# Sheet7.net
KiCad netlist of a schematic drawn in Altium Designer
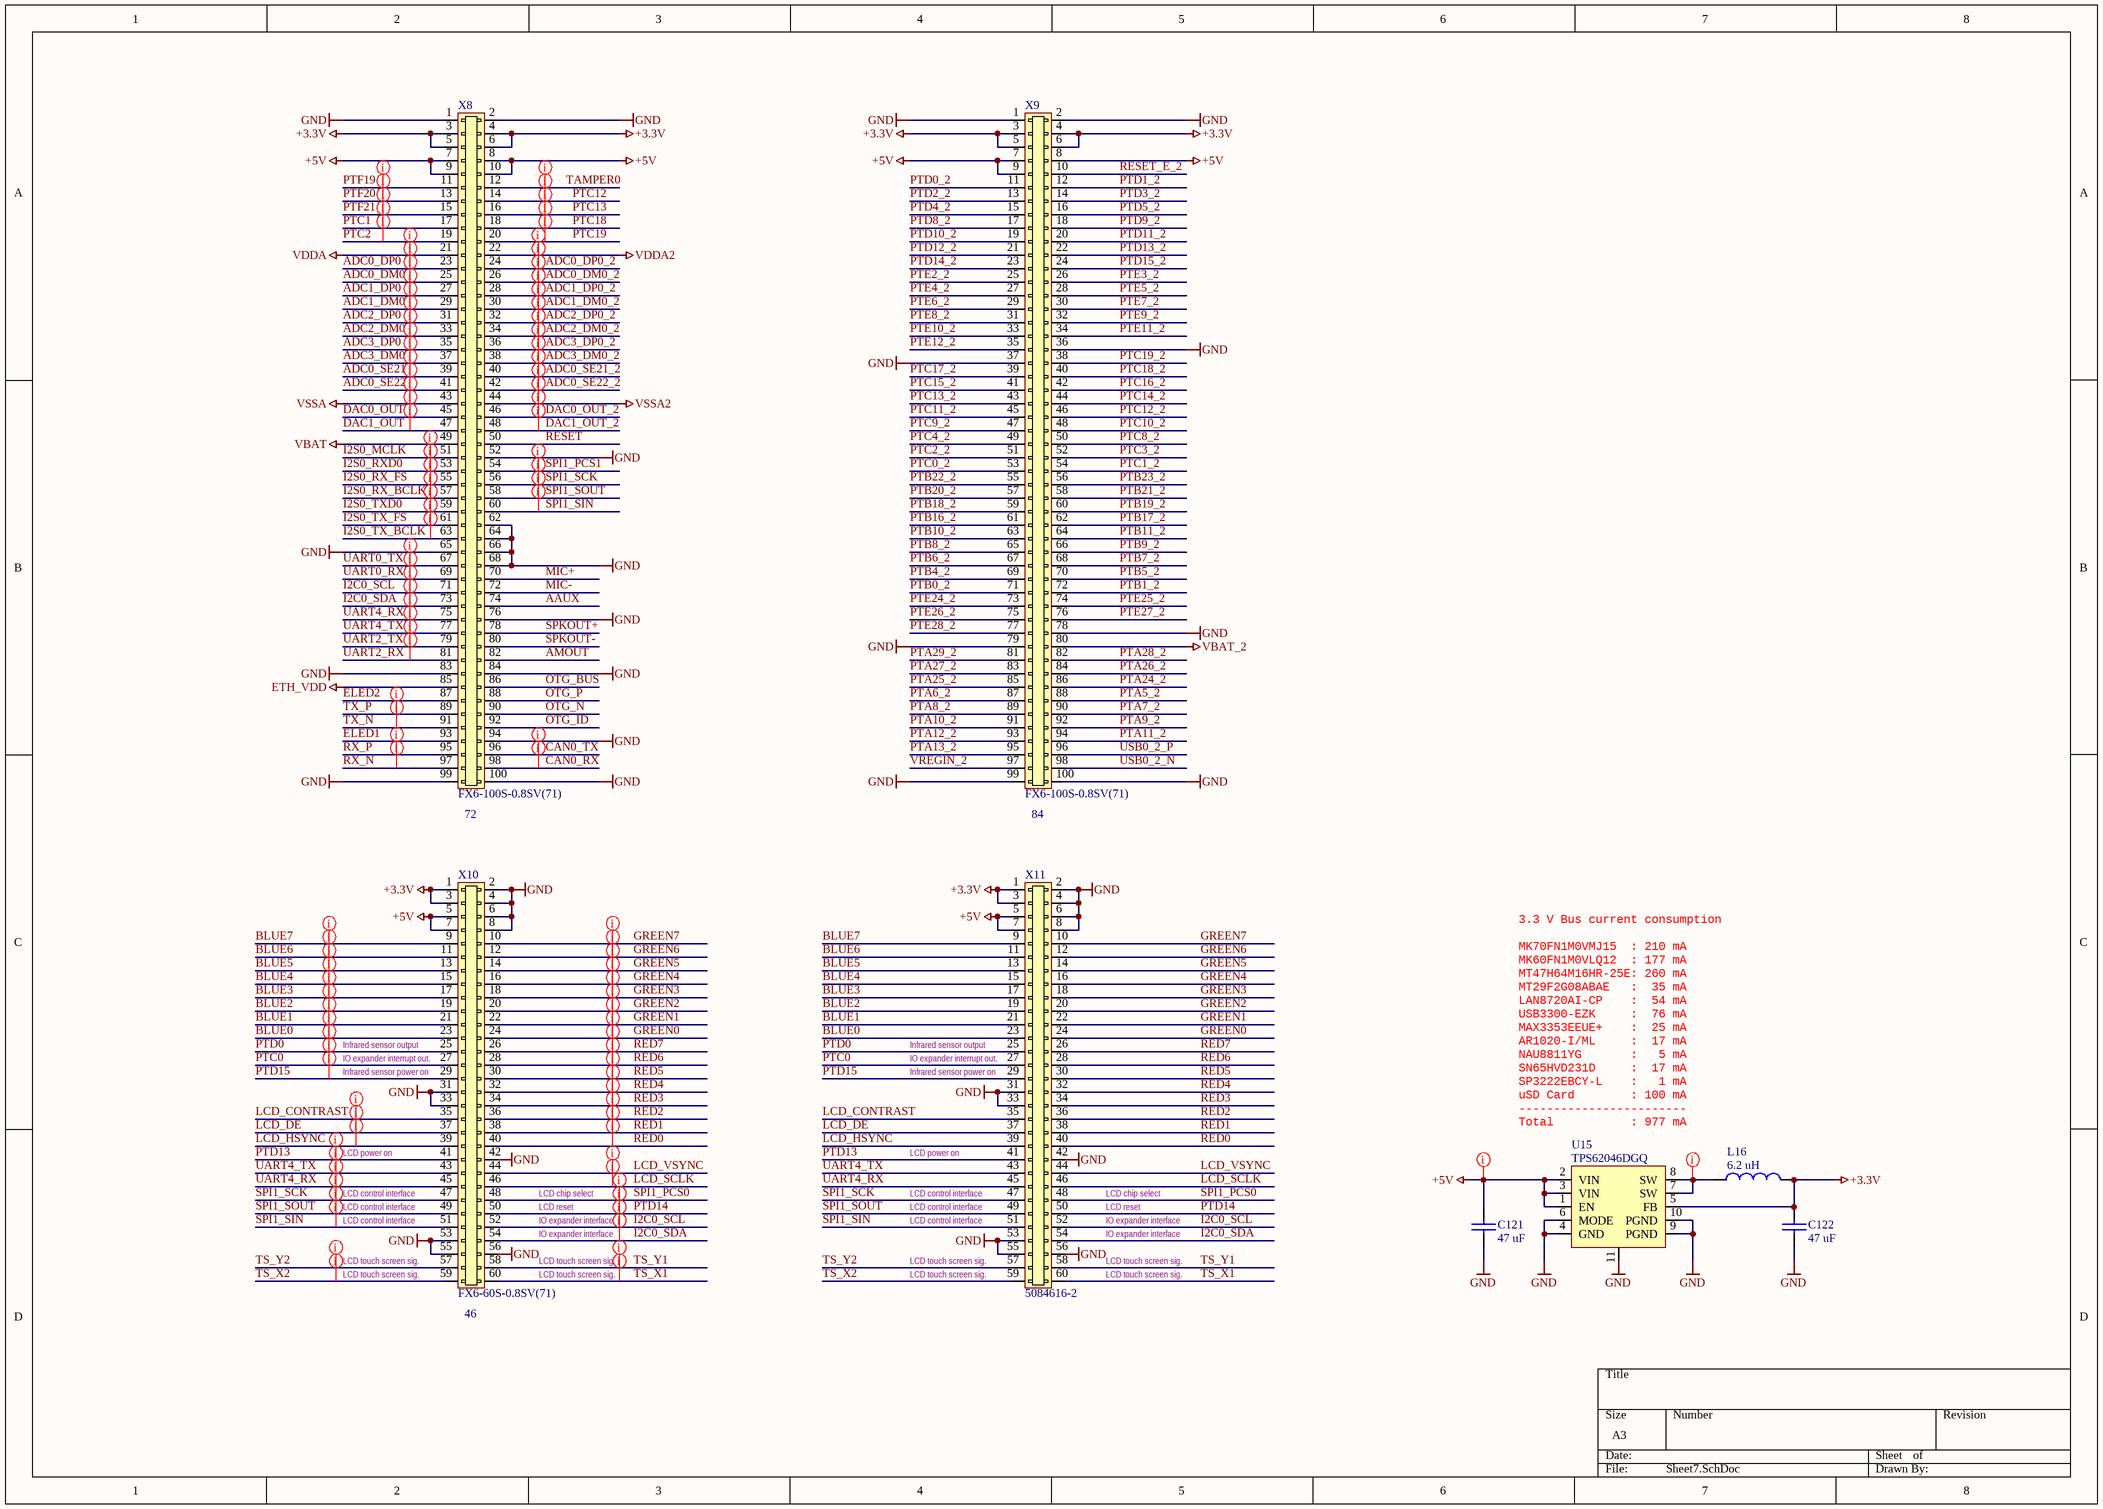
[diagram p0: Sheet7.SchDoc]

(export (version "E")
  (design (tool "Eeschema 10.0.6"))
  (components
    (comp (ref "C121")
      (value "47 uF")
      (footprint "3225[1210]")
      (description "47.0 uF, 10V, 10%, X7R, 1210")
      (fields
        (field (name "MANUFACTURER") "Murata Electronics North America")
        (field (name "TOLERANCE") "10%")
      )
      (libsource (lib "ea_Capacitors") (part "GRM32ER71A476KE15L"))
    )
    (comp (ref "C122")
      (value "47 uF")
      (footprint "3225[1210]")
      (description "47.0 uF, 10V, 10%, X7R, 1210")
      (fields
        (field (name "MANUFACTURER") "Murata Electronics North America")
        (field (name "TOLERANCE") "10%")
      )
      (libsource (lib "ea_Capacitors") (part "GRM32ER71A476KE15L"))
    )
    (comp (ref "L16")
      (value "6.2 uH")
      (footprint "CDRH6D38")
      (description "INDUCTOR POWER 6.2UH 2.50A SMD")
      (fields
        (field (name "MANUFACTURER") "Sumida America Components Inc")
        (field (name "PARTNUM") "308-2315-1-ND")
      )
      (libsource (lib "ea_Inductors") (part "CDRH6D38NP-6R2NC"))
    )
    (comp (ref "U15")
      (value "TPS62046DGQ")
      (footprint "TI-DGQ 10pin (R-PDSO-G10)")
      (description "REG BUCK SYNC 3.3V , 2.5..6V, 1.2A, -40..85 C, 10MSOP")
      (fields (field (name "MANUFACTURER") "Texas Instruments") (field (name "PARTNUM") "296-27023-5-ND"))
      (libsource (lib "ea_IC_Power_Reg_Ref_Sw") (part "TPS62046DGQ"))
    )
    (comp (ref "X8")
      (value "FX6-100S-0.8SV(71)")
      (footprint "FX6-100S-0.8SV(71)")
      (description "RECEPT 100POS .8MM SMD GOLD, 5mm, 6mm, 7 mm")
      (fields (field (name "MANUFACTURER") "Hirose Electric Co Ltd") (field (name "PARTNUM") "H10808-ND"))
      (libsource (lib "ea_Connectors") (part "FX6-100S-0.8SV(71)"))
    )
    (comp (ref "X9")
      (value "FX6-100S-0.8SV(71)")
      (footprint "FX6-100S-0.8SV(71)")
      (description "RECEPT 100POS .8MM SMD GOLD, 5mm, 6mm, 7 mm")
      (fields (field (name "MANUFACTURER") "Hirose Electric Co Ltd") (field (name "PARTNUM") "H10808-ND"))
      (libsource (lib "ea_Connectors") (part "FX6-100S-0.8SV(71)"))
    )
    (comp (ref "X10")
      (value "FX6-60S-0.8SV(71)")
      (footprint "FX6-60S-0.8SV(71)")
      (description "RECEPT 60POS .8MM W/BOSS")
      (fields (field (name "MANUFACTURER") "Hirose Electric Co Ltd") (field (name "PARTNUM") "H10806-ND"))
      (libsource (lib "ea_Connectors") (part "FX6-60S-0.8SV(71)"))
    )
    (comp (ref "X11")
      (value "5084616-2")
      (footprint "5084616-2")
      (description "Free Height (FH) Connectors 60P 13mm RECEPTACLE STACK HEIGHT 13-16mm")
      (fields (field (name "MANUFACTURER") "Tyco Electronics / AMP") (field (name "PARTNUM") "A99235CT-ND"))
      (libsource (lib "ea_Connectors") (part "5084616-2"))
    )
  )
  (nets
    (net (code "1") (name "+3.3V") (class "Default")
      (node (ref "C122") (pin "1") (pinfunction "1_1") (pintype "passive"))
      (node (ref "L16") (pin "2") (pinfunction "2_2") (pintype "passive"))
      (node (ref "U15") (pin "5") (pinfunction "FB_5") (pintype "passive"))
      (node (ref "X10") (pin "1") (pinfunction "1_1") (pintype "passive"))
      (node (ref "X10") (pin "3") (pinfunction "2_3") (pintype "passive"))
      (node (ref "X11") (pin "1") (pinfunction "1_1") (pintype "passive"))
      (node (ref "X11") (pin "3") (pinfunction "2_3") (pintype "passive"))
      (node (ref "X8") (pin "3") (pinfunction "2_3") (pintype "passive"))
      (node (ref "X8") (pin "4") (pinfunction "3_4") (pintype "passive"))
      (node (ref "X8") (pin "5") (pinfunction "3_5") (pintype "passive"))
      (node (ref "X8") (pin "6") (pinfunction "4_6") (pintype "passive"))
      (node (ref "X9") (pin "3") (pinfunction "2_3") (pintype "passive"))
      (node (ref "X9") (pin "4") (pinfunction "3_4") (pintype "passive"))
      (node (ref "X9") (pin "5") (pinfunction "3_5") (pintype "passive"))
      (node (ref "X9") (pin "6") (pinfunction "4_6") (pintype "passive"))
    )
    (net (code "2") (name "+5V") (class "Default")
      (node (ref "C121") (pin "1") (pinfunction "1_1") (pintype "passive"))
      (node (ref "U15") (pin "1") (pinfunction "EN_1") (pintype "passive"))
      (node (ref "U15") (pin "2") (pinfunction "VIN_2") (pintype "passive"))
      (node (ref "U15") (pin "3") (pinfunction "VIN_3") (pintype "passive"))
      (node (ref "X10") (pin "5") (pinfunction "3_5") (pintype "passive"))
      (node (ref "X10") (pin "7") (pinfunction "4_7") (pintype "passive"))
      (node (ref "X11") (pin "5") (pinfunction "3_5") (pintype "passive"))
      (node (ref "X11") (pin "7") (pinfunction "4_7") (pintype "passive"))
      (node (ref "X8") (pin "10") (pinfunction "6_10") (pintype "passive"))
      (node (ref "X8") (pin "7") (pinfunction "4_7") (pintype "passive"))
      (node (ref "X8") (pin "8") (pinfunction "5_8") (pintype "passive"))
      (node (ref "X8") (pin "9") (pinfunction "5_9") (pintype "passive"))
      (node (ref "X9") (pin "7") (pinfunction "4_7") (pintype "passive"))
      (node (ref "X9") (pin "8") (pinfunction "5_8") (pintype "passive"))
      (node (ref "X9") (pin "9") (pinfunction "5_9") (pintype "passive"))
    )
    (net (code "3") (name "/AAUX") (class "Default")
      (node (ref "X8") (pin "74") (pinfunction "38_74") (pintype "passive"))
    )
    (net (code "4") (name "/ADC0_DM0") (class "Default")
      (node (ref "X8") (pin "25") (pinfunction "13_25") (pintype "passive"))
    )
    (net (code "5") (name "/ADC0_DM0_2") (class "Default")
      (node (ref "X8") (pin "26") (pinfunction "14_26") (pintype "passive"))
    )
    (net (code "6") (name "/ADC0_DP0") (class "Default")
      (node (ref "X8") (pin "23") (pinfunction "12_23") (pintype "passive"))
    )
    (net (code "7") (name "/ADC0_DP0_2") (class "Default")
      (node (ref "X8") (pin "24") (pinfunction "13_24") (pintype "passive"))
    )
    (net (code "8") (name "/ADC0_SE21") (class "Default")
      (node (ref "X8") (pin "39") (pinfunction "20_39") (pintype "passive"))
    )
    (net (code "9") (name "/ADC0_SE21_2") (class "Default")
      (node (ref "X8") (pin "40") (pinfunction "21_40") (pintype "passive"))
    )
    (net (code "10") (name "/ADC0_SE22") (class "Default")
      (node (ref "X8") (pin "41") (pinfunction "21_41") (pintype "passive"))
    )
    (net (code "11") (name "/ADC0_SE22_2") (class "Default")
      (node (ref "X8") (pin "42") (pinfunction "22_42") (pintype "passive"))
    )
    (net (code "12") (name "/ADC1_DM0") (class "Default")
      (node (ref "X8") (pin "29") (pinfunction "15_29") (pintype "passive"))
    )
    (net (code "13") (name "/ADC1_DM0_2") (class "Default")
      (node (ref "X8") (pin "30") (pinfunction "16_30") (pintype "passive"))
    )
    (net (code "14") (name "/ADC1_DP0") (class "Default")
      (node (ref "X8") (pin "27") (pinfunction "14_27") (pintype "passive"))
    )
    (net (code "15") (name "/ADC1_DP0_2") (class "Default")
      (node (ref "X8") (pin "28") (pinfunction "15_28") (pintype "passive"))
    )
    (net (code "16") (name "/ADC2_DM0") (class "Default")
      (node (ref "X8") (pin "33") (pinfunction "17_33") (pintype "passive"))
    )
    (net (code "17") (name "/ADC2_DM0_2") (class "Default")
      (node (ref "X8") (pin "34") (pinfunction "18_34") (pintype "passive"))
    )
    (net (code "18") (name "/ADC2_DP0") (class "Default")
      (node (ref "X8") (pin "31") (pinfunction "16_31") (pintype "passive"))
    )
    (net (code "19") (name "/ADC2_DP0_2") (class "Default")
      (node (ref "X8") (pin "32") (pinfunction "17_32") (pintype "passive"))
    )
    (net (code "20") (name "/ADC3_DM0") (class "Default")
      (node (ref "X8") (pin "37") (pinfunction "19_37") (pintype "passive"))
    )
    (net (code "21") (name "/ADC3_DM0_2") (class "Default")
      (node (ref "X8") (pin "38") (pinfunction "20_38") (pintype "passive"))
    )
    (net (code "22") (name "/ADC3_DP0") (class "Default")
      (node (ref "X8") (pin "35") (pinfunction "18_35") (pintype "passive"))
    )
    (net (code "23") (name "/ADC3_DP0_2") (class "Default")
      (node (ref "X8") (pin "36") (pinfunction "19_36") (pintype "passive"))
    )
    (net (code "24") (name "/AMOUT") (class "Default")
      (node (ref "X8") (pin "82") (pinfunction "42_82") (pintype "passive"))
    )
    (net (code "25") (name "/BLUE0") (class "Default")
      (node (ref "X10") (pin "23") (pinfunction "12_23") (pintype "passive"))
      (node (ref "X11") (pin "23") (pinfunction "12_23") (pintype "passive"))
    )
    (net (code "26") (name "/BLUE1") (class "Default")
      (node (ref "X10") (pin "21") (pinfunction "11_21") (pintype "passive"))
      (node (ref "X11") (pin "21") (pinfunction "11_21") (pintype "passive"))
    )
    (net (code "27") (name "/BLUE2") (class "Default")
      (node (ref "X10") (pin "19") (pinfunction "10_19") (pintype "passive"))
      (node (ref "X11") (pin "19") (pinfunction "10_19") (pintype "passive"))
    )
    (net (code "28") (name "/BLUE3") (class "Default")
      (node (ref "X10") (pin "17") (pinfunction "9_17") (pintype "passive"))
      (node (ref "X11") (pin "17") (pinfunction "9_17") (pintype "passive"))
    )
    (net (code "29") (name "/BLUE4") (class "Default")
      (node (ref "X10") (pin "15") (pinfunction "8_15") (pintype "passive"))
      (node (ref "X11") (pin "15") (pinfunction "8_15") (pintype "passive"))
    )
    (net (code "30") (name "/BLUE5") (class "Default")
      (node (ref "X10") (pin "13") (pinfunction "7_13") (pintype "passive"))
      (node (ref "X11") (pin "13") (pinfunction "7_13") (pintype "passive"))
    )
    (net (code "31") (name "/BLUE6") (class "Default")
      (node (ref "X10") (pin "11") (pinfunction "6_11") (pintype "passive"))
      (node (ref "X11") (pin "11") (pinfunction "6_11") (pintype "passive"))
    )
    (net (code "32") (name "/BLUE7") (class "Default")
      (node (ref "X10") (pin "9") (pinfunction "5_9") (pintype "passive"))
      (node (ref "X11") (pin "9") (pinfunction "5_9") (pintype "passive"))
    )
    (net (code "33") (name "/CAN0_RX") (class "Default")
      (node (ref "X8") (pin "98") (pinfunction "50_98") (pintype "passive"))
    )
    (net (code "34") (name "/CAN0_TX") (class "Default")
      (node (ref "X8") (pin "96") (pinfunction "49_96") (pintype "passive"))
    )
    (net (code "35") (name "/DAC0_OUT") (class "Default")
      (node (ref "X8") (pin "45") (pinfunction "23_45") (pintype "passive"))
    )
    (net (code "36") (name "/DAC0_OUT_2") (class "Default")
      (node (ref "X8") (pin "46") (pinfunction "24_46") (pintype "passive"))
    )
    (net (code "37") (name "/DAC1_OUT") (class "Default")
      (node (ref "X8") (pin "47") (pinfunction "24_47") (pintype "passive"))
    )
    (net (code "38") (name "/DAC1_OUT_2") (class "Default")
      (node (ref "X8") (pin "48") (pinfunction "25_48") (pintype "passive"))
    )
    (net (code "39") (name "/ELED1") (class "Default")
      (node (ref "X8") (pin "93") (pinfunction "47_93") (pintype "passive"))
    )
    (net (code "40") (name "/ELED2") (class "Default")
      (node (ref "X8") (pin "87") (pinfunction "44_87") (pintype "passive"))
    )
    (net (code "41") (name "/GREEN0") (class "Default")
      (node (ref "X10") (pin "24") (pinfunction "13_24") (pintype "passive"))
      (node (ref "X11") (pin "24") (pinfunction "13_24") (pintype "passive"))
    )
    (net (code "42") (name "/GREEN1") (class "Default")
      (node (ref "X10") (pin "22") (pinfunction "12_22") (pintype "passive"))
      (node (ref "X11") (pin "22") (pinfunction "12_22") (pintype "passive"))
    )
    (net (code "43") (name "/GREEN2") (class "Default")
      (node (ref "X10") (pin "20") (pinfunction "11_20") (pintype "passive"))
      (node (ref "X11") (pin "20") (pinfunction "11_20") (pintype "passive"))
    )
    (net (code "44") (name "/GREEN3") (class "Default")
      (node (ref "X10") (pin "18") (pinfunction "10_18") (pintype "passive"))
      (node (ref "X11") (pin "18") (pinfunction "10_18") (pintype "passive"))
    )
    (net (code "45") (name "/GREEN4") (class "Default")
      (node (ref "X10") (pin "16") (pinfunction "9_16") (pintype "passive"))
      (node (ref "X11") (pin "16") (pinfunction "9_16") (pintype "passive"))
    )
    (net (code "46") (name "/GREEN5") (class "Default")
      (node (ref "X10") (pin "14") (pinfunction "8_14") (pintype "passive"))
      (node (ref "X11") (pin "14") (pinfunction "8_14") (pintype "passive"))
    )
    (net (code "47") (name "/GREEN6") (class "Default")
      (node (ref "X10") (pin "12") (pinfunction "7_12") (pintype "passive"))
      (node (ref "X11") (pin "12") (pinfunction "7_12") (pintype "passive"))
    )
    (net (code "48") (name "/GREEN7") (class "Default")
      (node (ref "X10") (pin "10") (pinfunction "6_10") (pintype "passive"))
      (node (ref "X11") (pin "10") (pinfunction "6_10") (pintype "passive"))
    )
    (net (code "49") (name "/I2C0_SCL") (class "Default")
      (node (ref "X10") (pin "52") (pinfunction "27_52") (pintype "passive"))
      (node (ref "X11") (pin "52") (pinfunction "27_52") (pintype "passive"))
      (node (ref "X8") (pin "71") (pinfunction "36_71") (pintype "passive"))
    )
    (net (code "50") (name "/I2C0_SDA") (class "Default")
      (node (ref "X10") (pin "54") (pinfunction "28_54") (pintype "passive"))
      (node (ref "X11") (pin "54") (pinfunction "28_54") (pintype "passive"))
      (node (ref "X8") (pin "73") (pinfunction "37_73") (pintype "passive"))
    )
    (net (code "51") (name "/I2S0_MCLK") (class "Default")
      (node (ref "X8") (pin "51") (pinfunction "26_51") (pintype "passive"))
    )
    (net (code "52") (name "/I2S0_RXD0") (class "Default")
      (node (ref "X8") (pin "53") (pinfunction "27_53") (pintype "passive"))
    )
    (net (code "53") (name "/I2S0_RX_BCLK") (class "Default")
      (node (ref "X8") (pin "57") (pinfunction "29_57") (pintype "passive"))
    )
    (net (code "54") (name "/I2S0_RX_FS") (class "Default")
      (node (ref "X8") (pin "55") (pinfunction "28_55") (pintype "passive"))
    )
    (net (code "55") (name "/I2S0_TXD0") (class "Default")
      (node (ref "X8") (pin "59") (pinfunction "30_59") (pintype "passive"))
    )
    (net (code "56") (name "/I2S0_TX_BCLK") (class "Default")
      (node (ref "X8") (pin "63") (pinfunction "32_63") (pintype "passive"))
    )
    (net (code "57") (name "/I2S0_TX_FS") (class "Default")
      (node (ref "X8") (pin "61") (pinfunction "31_61") (pintype "passive"))
    )
    (net (code "58") (name "/LCD_CONTRAST") (class "Default")
      (node (ref "X10") (pin "35") (pinfunction "18_35") (pintype "passive"))
      (node (ref "X11") (pin "35") (pinfunction "18_35") (pintype "passive"))
    )
    (net (code "59") (name "/LCD_DE") (class "Default")
      (node (ref "X10") (pin "37") (pinfunction "19_37") (pintype "passive"))
      (node (ref "X11") (pin "37") (pinfunction "19_37") (pintype "passive"))
    )
    (net (code "60") (name "/LCD_HSYNC") (class "Default")
      (node (ref "X10") (pin "39") (pinfunction "20_39") (pintype "passive"))
      (node (ref "X11") (pin "39") (pinfunction "20_39") (pintype "passive"))
    )
    (net (code "61") (name "/LCD_SCLK") (class "Default")
      (node (ref "X10") (pin "46") (pinfunction "24_46") (pintype "passive"))
      (node (ref "X11") (pin "46") (pinfunction "24_46") (pintype "passive"))
    )
    (net (code "62") (name "/LCD_VSYNC") (class "Default")
      (node (ref "X10") (pin "44") (pinfunction "23_44") (pintype "passive"))
      (node (ref "X11") (pin "44") (pinfunction "23_44") (pintype "passive"))
    )
    (net (code "63") (name "/MIC+") (class "Default")
      (node (ref "X8") (pin "70") (pinfunction "36_70") (pintype "passive"))
    )
    (net (code "64") (name "/MIC-") (class "Default")
      (node (ref "X8") (pin "72") (pinfunction "37_72") (pintype "passive"))
    )
    (net (code "65") (name "/OTG_BUS") (class "Default")
      (node (ref "X8") (pin "86") (pinfunction "44_86") (pintype "passive"))
    )
    (net (code "66") (name "/OTG_ID") (class "Default")
      (node (ref "X8") (pin "92") (pinfunction "47_92") (pintype "passive"))
    )
    (net (code "67") (name "/OTG_N") (class "Default")
      (node (ref "X8") (pin "90") (pinfunction "46_90") (pintype "passive"))
    )
    (net (code "68") (name "/OTG_P") (class "Default")
      (node (ref "X8") (pin "88") (pinfunction "45_88") (pintype "passive"))
    )
    (net (code "69") (name "/PTA5_2") (class "Default")
      (node (ref "X9") (pin "88") (pinfunction "45_88") (pintype "passive"))
    )
    (net (code "70") (name "/PTA6_2") (class "Default")
      (node (ref "X9") (pin "87") (pinfunction "44_87") (pintype "passive"))
    )
    (net (code "71") (name "/PTA7_2") (class "Default")
      (node (ref "X9") (pin "90") (pinfunction "46_90") (pintype "passive"))
    )
    (net (code "72") (name "/PTA8_2") (class "Default")
      (node (ref "X9") (pin "89") (pinfunction "45_89") (pintype "passive"))
    )
    (net (code "73") (name "/PTA9_2") (class "Default")
      (node (ref "X9") (pin "92") (pinfunction "47_92") (pintype "passive"))
    )
    (net (code "74") (name "/PTA10_2") (class "Default")
      (node (ref "X9") (pin "91") (pinfunction "46_91") (pintype "passive"))
    )
    (net (code "75") (name "/PTA11_2") (class "Default")
      (node (ref "X9") (pin "94") (pinfunction "48_94") (pintype "passive"))
    )
    (net (code "76") (name "/PTA12_2") (class "Default")
      (node (ref "X9") (pin "93") (pinfunction "47_93") (pintype "passive"))
    )
    (net (code "77") (name "/PTA13_2") (class "Default")
      (node (ref "X9") (pin "95") (pinfunction "48_95") (pintype "passive"))
    )
    (net (code "78") (name "/PTA24_2") (class "Default")
      (node (ref "X9") (pin "86") (pinfunction "44_86") (pintype "passive"))
    )
    (net (code "79") (name "/PTA25_2") (class "Default")
      (node (ref "X9") (pin "85") (pinfunction "43_85") (pintype "passive"))
    )
    (net (code "80") (name "/PTA26_2") (class "Default")
      (node (ref "X9") (pin "84") (pinfunction "43_84") (pintype "passive"))
    )
    (net (code "81") (name "/PTA27_2") (class "Default")
      (node (ref "X9") (pin "83") (pinfunction "42_83") (pintype "passive"))
    )
    (net (code "82") (name "/PTA28_2") (class "Default")
      (node (ref "X9") (pin "82") (pinfunction "42_82") (pintype "passive"))
    )
    (net (code "83") (name "/PTA29_2") (class "Default")
      (node (ref "X9") (pin "81") (pinfunction "41_81") (pintype "passive"))
    )
    (net (code "84") (name "/PTB0_2") (class "Default")
      (node (ref "X9") (pin "71") (pinfunction "36_71") (pintype "passive"))
    )
    (net (code "85") (name "/PTB1_2") (class "Default")
      (node (ref "X9") (pin "72") (pinfunction "37_72") (pintype "passive"))
    )
    (net (code "86") (name "/PTB4_2") (class "Default")
      (node (ref "X9") (pin "69") (pinfunction "35_69") (pintype "passive"))
    )
    (net (code "87") (name "/PTB5_2") (class "Default")
      (node (ref "X9") (pin "70") (pinfunction "36_70") (pintype "passive"))
    )
    (net (code "88") (name "/PTB6_2") (class "Default")
      (node (ref "X9") (pin "67") (pinfunction "34_67") (pintype "passive"))
    )
    (net (code "89") (name "/PTB7_2") (class "Default")
      (node (ref "X9") (pin "68") (pinfunction "35_68") (pintype "passive"))
    )
    (net (code "90") (name "/PTB8_2") (class "Default")
      (node (ref "X9") (pin "65") (pinfunction "33_65") (pintype "passive"))
    )
    (net (code "91") (name "/PTB9_2") (class "Default")
      (node (ref "X9") (pin "66") (pinfunction "34_66") (pintype "passive"))
    )
    (net (code "92") (name "/PTB10_2") (class "Default")
      (node (ref "X9") (pin "63") (pinfunction "32_63") (pintype "passive"))
    )
    (net (code "93") (name "/PTB11_2") (class "Default")
      (node (ref "X9") (pin "64") (pinfunction "33_64") (pintype "passive"))
    )
    (net (code "94") (name "/PTB16_2") (class "Default")
      (node (ref "X9") (pin "61") (pinfunction "31_61") (pintype "passive"))
    )
    (net (code "95") (name "/PTB17_2") (class "Default")
      (node (ref "X9") (pin "62") (pinfunction "32_62") (pintype "passive"))
    )
    (net (code "96") (name "/PTB18_2") (class "Default")
      (node (ref "X9") (pin "59") (pinfunction "30_59") (pintype "passive"))
    )
    (net (code "97") (name "/PTB19_2") (class "Default")
      (node (ref "X9") (pin "60") (pinfunction "31_60") (pintype "passive"))
    )
    (net (code "98") (name "/PTB20_2") (class "Default")
      (node (ref "X9") (pin "57") (pinfunction "29_57") (pintype "passive"))
    )
    (net (code "99") (name "/PTB21_2") (class "Default")
      (node (ref "X9") (pin "58") (pinfunction "30_58") (pintype "passive"))
    )
    (net (code "100") (name "/PTB22_2") (class "Default")
      (node (ref "X9") (pin "55") (pinfunction "28_55") (pintype "passive"))
    )
    (net (code "101") (name "/PTB23_2") (class "Default")
      (node (ref "X9") (pin "56") (pinfunction "29_56") (pintype "passive"))
    )
    (net (code "102") (name "/PTC0") (class "Default")
      (node (ref "X10") (pin "27") (pinfunction "14_27") (pintype "passive"))
      (node (ref "X11") (pin "27") (pinfunction "14_27") (pintype "passive"))
    )
    (net (code "103") (name "/PTC0_2") (class "Default")
      (node (ref "X9") (pin "53") (pinfunction "27_53") (pintype "passive"))
    )
    (net (code "104") (name "/PTC1") (class "Default")
      (node (ref "X8") (pin "17") (pinfunction "9_17") (pintype "passive"))
    )
    (net (code "105") (name "/PTC1_2") (class "Default")
      (node (ref "X9") (pin "54") (pinfunction "28_54") (pintype "passive"))
    )
    (net (code "106") (name "/PTC2") (class "Default")
      (node (ref "X8") (pin "19") (pinfunction "10_19") (pintype "passive"))
    )
    (net (code "107") (name "/PTC2_2") (class "Default")
      (node (ref "X9") (pin "51") (pinfunction "26_51") (pintype "passive"))
    )
    (net (code "108") (name "/PTC3_2") (class "Default")
      (node (ref "X9") (pin "52") (pinfunction "27_52") (pintype "passive"))
    )
    (net (code "109") (name "/PTC4_2") (class "Default")
      (node (ref "X9") (pin "49") (pinfunction "25_49") (pintype "passive"))
    )
    (net (code "110") (name "/PTC8_2") (class "Default")
      (node (ref "X9") (pin "50") (pinfunction "26_50") (pintype "passive"))
    )
    (net (code "111") (name "/PTC9_2") (class "Default")
      (node (ref "X9") (pin "47") (pinfunction "24_47") (pintype "passive"))
    )
    (net (code "112") (name "/PTC10_2") (class "Default")
      (node (ref "X9") (pin "48") (pinfunction "25_48") (pintype "passive"))
    )
    (net (code "113") (name "/PTC11_2") (class "Default")
      (node (ref "X9") (pin "45") (pinfunction "23_45") (pintype "passive"))
    )
    (net (code "114") (name "/PTC12") (class "Default")
      (node (ref "X8") (pin "14") (pinfunction "8_14") (pintype "passive"))
    )
    (net (code "115") (name "/PTC12_2") (class "Default")
      (node (ref "X9") (pin "46") (pinfunction "24_46") (pintype "passive"))
    )
    (net (code "116") (name "/PTC13") (class "Default")
      (node (ref "X8") (pin "16") (pinfunction "9_16") (pintype "passive"))
    )
    (net (code "117") (name "/PTC13_2") (class "Default")
      (node (ref "X9") (pin "43") (pinfunction "22_43") (pintype "passive"))
    )
    (net (code "118") (name "/PTC14_2") (class "Default")
      (node (ref "X9") (pin "44") (pinfunction "23_44") (pintype "passive"))
    )
    (net (code "119") (name "/PTC15_2") (class "Default")
      (node (ref "X9") (pin "41") (pinfunction "21_41") (pintype "passive"))
    )
    (net (code "120") (name "/PTC16_2") (class "Default")
      (node (ref "X9") (pin "42") (pinfunction "22_42") (pintype "passive"))
    )
    (net (code "121") (name "/PTC17_2") (class "Default")
      (node (ref "X9") (pin "39") (pinfunction "20_39") (pintype "passive"))
    )
    (net (code "122") (name "/PTC18") (class "Default")
      (node (ref "X8") (pin "18") (pinfunction "10_18") (pintype "passive"))
    )
    (net (code "123") (name "/PTC18_2") (class "Default")
      (node (ref "X9") (pin "40") (pinfunction "21_40") (pintype "passive"))
    )
    (net (code "124") (name "/PTC19") (class "Default")
      (node (ref "X8") (pin "20") (pinfunction "11_20") (pintype "passive"))
    )
    (net (code "125") (name "/PTC19_2") (class "Default")
      (node (ref "X9") (pin "38") (pinfunction "20_38") (pintype "passive"))
    )
    (net (code "126") (name "/PTD0") (class "Default")
      (node (ref "X10") (pin "25") (pinfunction "13_25") (pintype "passive"))
      (node (ref "X11") (pin "25") (pinfunction "13_25") (pintype "passive"))
    )
    (net (code "127") (name "/PTD0_2") (class "Default")
      (node (ref "X9") (pin "11") (pinfunction "6_11") (pintype "passive"))
    )
    (net (code "128") (name "/PTD1_2") (class "Default")
      (node (ref "X9") (pin "12") (pinfunction "7_12") (pintype "passive"))
    )
    (net (code "129") (name "/PTD2_2") (class "Default")
      (node (ref "X9") (pin "13") (pinfunction "7_13") (pintype "passive"))
    )
    (net (code "130") (name "/PTD3_2") (class "Default")
      (node (ref "X9") (pin "14") (pinfunction "8_14") (pintype "passive"))
    )
    (net (code "131") (name "/PTD4_2") (class "Default")
      (node (ref "X9") (pin "15") (pinfunction "8_15") (pintype "passive"))
    )
    (net (code "132") (name "/PTD5_2") (class "Default")
      (node (ref "X9") (pin "16") (pinfunction "9_16") (pintype "passive"))
    )
    (net (code "133") (name "/PTD8_2") (class "Default")
      (node (ref "X9") (pin "17") (pinfunction "9_17") (pintype "passive"))
    )
    (net (code "134") (name "/PTD9_2") (class "Default")
      (node (ref "X9") (pin "18") (pinfunction "10_18") (pintype "passive"))
    )
    (net (code "135") (name "/PTD10_2") (class "Default")
      (node (ref "X9") (pin "19") (pinfunction "10_19") (pintype "passive"))
    )
    (net (code "136") (name "/PTD11_2") (class "Default")
      (node (ref "X9") (pin "20") (pinfunction "11_20") (pintype "passive"))
    )
    (net (code "137") (name "/PTD12_2") (class "Default")
      (node (ref "X9") (pin "21") (pinfunction "11_21") (pintype "passive"))
    )
    (net (code "138") (name "/PTD13") (class "Default")
      (node (ref "X10") (pin "41") (pinfunction "21_41") (pintype "passive"))
      (node (ref "X11") (pin "41") (pinfunction "21_41") (pintype "passive"))
    )
    (net (code "139") (name "/PTD13_2") (class "Default")
      (node (ref "X9") (pin "22") (pinfunction "12_22") (pintype "passive"))
    )
    (net (code "140") (name "/PTD14") (class "Default")
      (node (ref "X10") (pin "50") (pinfunction "26_50") (pintype "passive"))
      (node (ref "X11") (pin "50") (pinfunction "26_50") (pintype "passive"))
    )
    (net (code "141") (name "/PTD14_2") (class "Default")
      (node (ref "X9") (pin "23") (pinfunction "12_23") (pintype "passive"))
    )
    (net (code "142") (name "/PTD15") (class "Default")
      (node (ref "X10") (pin "29") (pinfunction "15_29") (pintype "passive"))
      (node (ref "X11") (pin "29") (pinfunction "15_29") (pintype "passive"))
    )
    (net (code "143") (name "/PTD15_2") (class "Default")
      (node (ref "X9") (pin "24") (pinfunction "13_24") (pintype "passive"))
    )
    (net (code "144") (name "/PTE2_2") (class "Default")
      (node (ref "X9") (pin "25") (pinfunction "13_25") (pintype "passive"))
    )
    (net (code "145") (name "/PTE3_2") (class "Default")
      (node (ref "X9") (pin "26") (pinfunction "14_26") (pintype "passive"))
    )
    (net (code "146") (name "/PTE4_2") (class "Default")
      (node (ref "X9") (pin "27") (pinfunction "14_27") (pintype "passive"))
    )
    (net (code "147") (name "/PTE5_2") (class "Default")
      (node (ref "X9") (pin "28") (pinfunction "15_28") (pintype "passive"))
    )
    (net (code "148") (name "/PTE6_2") (class "Default")
      (node (ref "X9") (pin "29") (pinfunction "15_29") (pintype "passive"))
    )
    (net (code "149") (name "/PTE7_2") (class "Default")
      (node (ref "X9") (pin "30") (pinfunction "16_30") (pintype "passive"))
    )
    (net (code "150") (name "/PTE8_2") (class "Default")
      (node (ref "X9") (pin "31") (pinfunction "16_31") (pintype "passive"))
    )
    (net (code "151") (name "/PTE9_2") (class "Default")
      (node (ref "X9") (pin "32") (pinfunction "17_32") (pintype "passive"))
    )
    (net (code "152") (name "/PTE10_2") (class "Default")
      (node (ref "X9") (pin "33") (pinfunction "17_33") (pintype "passive"))
    )
    (net (code "153") (name "/PTE11_2") (class "Default")
      (node (ref "X9") (pin "34") (pinfunction "18_34") (pintype "passive"))
    )
    (net (code "154") (name "/PTE12_2") (class "Default")
      (node (ref "X9") (pin "35") (pinfunction "18_35") (pintype "passive"))
    )
    (net (code "155") (name "/PTE24_2") (class "Default")
      (node (ref "X9") (pin "73") (pinfunction "37_73") (pintype "passive"))
    )
    (net (code "156") (name "/PTE25_2") (class "Default")
      (node (ref "X9") (pin "74") (pinfunction "38_74") (pintype "passive"))
    )
    (net (code "157") (name "/PTE26_2") (class "Default")
      (node (ref "X9") (pin "75") (pinfunction "38_75") (pintype "passive"))
    )
    (net (code "158") (name "/PTE27_2") (class "Default")
      (node (ref "X9") (pin "76") (pinfunction "39_76") (pintype "passive"))
    )
    (net (code "159") (name "/PTE28_2") (class "Default")
      (node (ref "X9") (pin "77") (pinfunction "39_77") (pintype "passive"))
    )
    (net (code "160") (name "/PTF19") (class "Default")
      (node (ref "X8") (pin "11") (pinfunction "6_11") (pintype "passive"))
    )
    (net (code "161") (name "/PTF20") (class "Default")
      (node (ref "X8") (pin "13") (pinfunction "7_13") (pintype "passive"))
    )
    (net (code "162") (name "/PTF21") (class "Default")
      (node (ref "X8") (pin "15") (pinfunction "8_15") (pintype "passive"))
    )
    (net (code "163") (name "/RED0") (class "Default")
      (node (ref "X10") (pin "40") (pinfunction "21_40") (pintype "passive"))
      (node (ref "X11") (pin "40") (pinfunction "21_40") (pintype "passive"))
    )
    (net (code "164") (name "/RED1") (class "Default")
      (node (ref "X10") (pin "38") (pinfunction "20_38") (pintype "passive"))
      (node (ref "X11") (pin "38") (pinfunction "20_38") (pintype "passive"))
    )
    (net (code "165") (name "/RED2") (class "Default")
      (node (ref "X10") (pin "36") (pinfunction "19_36") (pintype "passive"))
      (node (ref "X11") (pin "36") (pinfunction "19_36") (pintype "passive"))
    )
    (net (code "166") (name "/RED3") (class "Default")
      (node (ref "X10") (pin "34") (pinfunction "18_34") (pintype "passive"))
      (node (ref "X11") (pin "34") (pinfunction "18_34") (pintype "passive"))
    )
    (net (code "167") (name "/RED4") (class "Default")
      (node (ref "X10") (pin "32") (pinfunction "17_32") (pintype "passive"))
      (node (ref "X11") (pin "32") (pinfunction "17_32") (pintype "passive"))
    )
    (net (code "168") (name "/RED5") (class "Default")
      (node (ref "X10") (pin "30") (pinfunction "16_30") (pintype "passive"))
      (node (ref "X11") (pin "30") (pinfunction "16_30") (pintype "passive"))
    )
    (net (code "169") (name "/RED6") (class "Default")
      (node (ref "X10") (pin "28") (pinfunction "15_28") (pintype "passive"))
      (node (ref "X11") (pin "28") (pinfunction "15_28") (pintype "passive"))
    )
    (net (code "170") (name "/RED7") (class "Default")
      (node (ref "X10") (pin "26") (pinfunction "14_26") (pintype "passive"))
      (node (ref "X11") (pin "26") (pinfunction "14_26") (pintype "passive"))
    )
    (net (code "171") (name "/RESET") (class "Default")
      (node (ref "X8") (pin "50") (pinfunction "26_50") (pintype "passive"))
    )
    (net (code "172") (name "/RESET_E_2") (class "Default")
      (node (ref "X9") (pin "10") (pinfunction "6_10") (pintype "passive"))
    )
    (net (code "173") (name "/RX_N") (class "Default")
      (node (ref "X8") (pin "97") (pinfunction "49_97") (pintype "passive"))
    )
    (net (code "174") (name "/RX_P") (class "Default")
      (node (ref "X8") (pin "95") (pinfunction "48_95") (pintype "passive"))
    )
    (net (code "175") (name "/SPI1_PCS0") (class "Default")
      (node (ref "X10") (pin "48") (pinfunction "25_48") (pintype "passive"))
      (node (ref "X11") (pin "48") (pinfunction "25_48") (pintype "passive"))
    )
    (net (code "176") (name "/SPI1_PCS1") (class "Default")
      (node (ref "X8") (pin "54") (pinfunction "28_54") (pintype "passive"))
    )
    (net (code "177") (name "/SPI1_SCK") (class "Default")
      (node (ref "X10") (pin "47") (pinfunction "24_47") (pintype "passive"))
      (node (ref "X11") (pin "47") (pinfunction "24_47") (pintype "passive"))
      (node (ref "X8") (pin "56") (pinfunction "29_56") (pintype "passive"))
    )
    (net (code "178") (name "/SPI1_SIN") (class "Default")
      (node (ref "X10") (pin "51") (pinfunction "26_51") (pintype "passive"))
      (node (ref "X11") (pin "51") (pinfunction "26_51") (pintype "passive"))
      (node (ref "X8") (pin "60") (pinfunction "31_60") (pintype "passive"))
    )
    (net (code "179") (name "/SPI1_SOUT") (class "Default")
      (node (ref "X10") (pin "49") (pinfunction "25_49") (pintype "passive"))
      (node (ref "X11") (pin "49") (pinfunction "25_49") (pintype "passive"))
      (node (ref "X8") (pin "58") (pinfunction "30_58") (pintype "passive"))
    )
    (net (code "180") (name "/SPKOUT+") (class "Default")
      (node (ref "X8") (pin "78") (pinfunction "40_78") (pintype "passive"))
    )
    (net (code "181") (name "/SPKOUT-") (class "Default")
      (node (ref "X8") (pin "80") (pinfunction "41_80") (pintype "passive"))
    )
    (net (code "182") (name "/TAMPER0") (class "Default")
      (node (ref "X8") (pin "12") (pinfunction "7_12") (pintype "passive"))
    )
    (net (code "183") (name "/TS_X1") (class "Default")
      (node (ref "X10") (pin "60") (pinfunction "31_60") (pintype "passive"))
      (node (ref "X11") (pin "60") (pinfunction "31_60") (pintype "passive"))
    )
    (net (code "184") (name "/TS_X2") (class "Default")
      (node (ref "X10") (pin "59") (pinfunction "30_59") (pintype "passive"))
      (node (ref "X11") (pin "59") (pinfunction "30_59") (pintype "passive"))
    )
    (net (code "185") (name "/TS_Y1") (class "Default")
      (node (ref "X10") (pin "58") (pinfunction "30_58") (pintype "passive"))
      (node (ref "X11") (pin "58") (pinfunction "30_58") (pintype "passive"))
    )
    (net (code "186") (name "/TS_Y2") (class "Default")
      (node (ref "X10") (pin "57") (pinfunction "29_57") (pintype "passive"))
      (node (ref "X11") (pin "57") (pinfunction "29_57") (pintype "passive"))
    )
    (net (code "187") (name "/TX_N") (class "Default")
      (node (ref "X8") (pin "91") (pinfunction "46_91") (pintype "passive"))
    )
    (net (code "188") (name "/TX_P") (class "Default")
      (node (ref "X8") (pin "89") (pinfunction "45_89") (pintype "passive"))
    )
    (net (code "189") (name "/UART0_RX") (class "Default")
      (node (ref "X8") (pin "69") (pinfunction "35_69") (pintype "passive"))
    )
    (net (code "190") (name "/UART0_TX") (class "Default")
      (node (ref "X8") (pin "67") (pinfunction "34_67") (pintype "passive"))
    )
    (net (code "191") (name "/UART2_RX") (class "Default")
      (node (ref "X8") (pin "81") (pinfunction "41_81") (pintype "passive"))
    )
    (net (code "192") (name "/UART2_TX") (class "Default")
      (node (ref "X8") (pin "79") (pinfunction "40_79") (pintype "passive"))
    )
    (net (code "193") (name "/UART4_RX") (class "Default")
      (node (ref "X10") (pin "45") (pinfunction "23_45") (pintype "passive"))
      (node (ref "X11") (pin "45") (pinfunction "23_45") (pintype "passive"))
      (node (ref "X8") (pin "75") (pinfunction "38_75") (pintype "passive"))
    )
    (net (code "194") (name "/UART4_TX") (class "Default")
      (node (ref "X10") (pin "43") (pinfunction "22_43") (pintype "passive"))
      (node (ref "X11") (pin "43") (pinfunction "22_43") (pintype "passive"))
      (node (ref "X8") (pin "77") (pinfunction "39_77") (pintype "passive"))
    )
    (net (code "195") (name "/USB0_2_N") (class "Default")
      (node (ref "X9") (pin "98") (pinfunction "50_98") (pintype "passive"))
    )
    (net (code "196") (name "/USB0_2_P") (class "Default")
      (node (ref "X9") (pin "96") (pinfunction "49_96") (pintype "passive"))
    )
    (net (code "197") (name "/VREGIN_2") (class "Default")
      (node (ref "X9") (pin "97") (pinfunction "49_97") (pintype "passive"))
    )
    (net (code "198") (name "ETH_VDD") (class "Default")
      (node (ref "X8") (pin "85") (pinfunction "43_85") (pintype "passive"))
    )
    (net (code "199") (name "GND") (class "Default")
      (node (ref "C121") (pin "2") (pinfunction "2_2") (pintype "passive"))
      (node (ref "C122") (pin "2") (pinfunction "2_2") (pintype "passive"))
      (node (ref "U15") (pin "10") (pinfunction "PGND_10") (pintype "passive"))
      (node (ref "U15") (pin "11") (pinfunction "PAD_11") (pintype "passive"))
      (node (ref "U15") (pin "4") (pinfunction "GND_4") (pintype "passive"))
      (node (ref "U15") (pin "6") (pinfunction "MODE_6") (pintype "passive"))
      (node (ref "U15") (pin "9") (pinfunction "PGND_9") (pintype "passive"))
      (node (ref "X10") (pin "2") (pinfunction "2_2") (pintype "passive"))
      (node (ref "X10") (pin "31") (pinfunction "16_31") (pintype "passive"))
      (node (ref "X10") (pin "33") (pinfunction "17_33") (pintype "passive"))
      (node (ref "X10") (pin "4") (pinfunction "3_4") (pintype "passive"))
      (node (ref "X10") (pin "42") (pinfunction "22_42") (pintype "passive"))
      (node (ref "X10") (pin "53") (pinfunction "27_53") (pintype "passive"))
      (node (ref "X10") (pin "55") (pinfunction "28_55") (pintype "passive"))
      (node (ref "X10") (pin "56") (pinfunction "29_56") (pintype "passive"))
      (node (ref "X10") (pin "6") (pinfunction "4_6") (pintype "passive"))
      (node (ref "X10") (pin "8") (pinfunction "5_8") (pintype "passive"))
      (node (ref "X11") (pin "2") (pinfunction "2_2") (pintype "passive"))
      (node (ref "X11") (pin "31") (pinfunction "16_31") (pintype "passive"))
      (node (ref "X11") (pin "33") (pinfunction "17_33") (pintype "passive"))
      (node (ref "X11") (pin "4") (pinfunction "3_4") (pintype "passive"))
      (node (ref "X11") (pin "42") (pinfunction "22_42") (pintype "passive"))
      (node (ref "X11") (pin "53") (pinfunction "27_53") (pintype "passive"))
      (node (ref "X11") (pin "55") (pinfunction "28_55") (pintype "passive"))
      (node (ref "X11") (pin "56") (pinfunction "29_56") (pintype "passive"))
      (node (ref "X11") (pin "6") (pinfunction "4_6") (pintype "passive"))
      (node (ref "X11") (pin "8") (pinfunction "5_8") (pintype "passive"))
      (node (ref "X8") (pin "1") (pinfunction "1_1") (pintype "passive"))
      (node (ref "X8") (pin "100") (pinfunction "51_100") (pintype "passive"))
      (node (ref "X8") (pin "2") (pinfunction "2_2") (pintype "passive"))
      (node (ref "X8") (pin "52") (pinfunction "27_52") (pintype "passive"))
      (node (ref "X8") (pin "62") (pinfunction "32_62") (pintype "passive"))
      (node (ref "X8") (pin "64") (pinfunction "33_64") (pintype "passive"))
      (node (ref "X8") (pin "65") (pinfunction "33_65") (pintype "passive"))
      (node (ref "X8") (pin "66") (pinfunction "34_66") (pintype "passive"))
      (node (ref "X8") (pin "68") (pinfunction "35_68") (pintype "passive"))
      (node (ref "X8") (pin "76") (pinfunction "39_76") (pintype "passive"))
      (node (ref "X8") (pin "83") (pinfunction "42_83") (pintype "passive"))
      (node (ref "X8") (pin "84") (pinfunction "43_84") (pintype "passive"))
      (node (ref "X8") (pin "94") (pinfunction "48_94") (pintype "passive"))
      (node (ref "X8") (pin "99") (pinfunction "50_99") (pintype "passive"))
      (node (ref "X9") (pin "1") (pinfunction "1_1") (pintype "passive"))
      (node (ref "X9") (pin "100") (pinfunction "51_100") (pintype "passive"))
      (node (ref "X9") (pin "2") (pinfunction "2_2") (pintype "passive"))
      (node (ref "X9") (pin "36") (pinfunction "19_36") (pintype "passive"))
      (node (ref "X9") (pin "37") (pinfunction "19_37") (pintype "passive"))
      (node (ref "X9") (pin "78") (pinfunction "40_78") (pintype "passive"))
      (node (ref "X9") (pin "79") (pinfunction "40_79") (pintype "passive"))
      (node (ref "X9") (pin "99") (pinfunction "50_99") (pintype "passive"))
    )
    (net (code "200") (name "Net-(L16-Pad1)") (class "Default")
      (node (ref "L16") (pin "1") (pinfunction "1_1") (pintype "passive"))
      (node (ref "U15") (pin "7") (pinfunction "SW_7") (pintype "passive"))
      (node (ref "U15") (pin "8") (pinfunction "SW_8") (pintype "passive"))
    )
    (net (code "201") (name "VBAT") (class "Default")
      (node (ref "X8") (pin "49") (pinfunction "25_49") (pintype "passive"))
    )
    (net (code "202") (name "VBAT_2") (class "Default")
      (node (ref "X9") (pin "80") (pinfunction "41_80") (pintype "passive"))
    )
    (net (code "203") (name "VDDA") (class "Default")
      (node (ref "X8") (pin "21") (pinfunction "11_21") (pintype "passive"))
    )
    (net (code "204") (name "VDDA2") (class "Default")
      (node (ref "X8") (pin "22") (pinfunction "12_22") (pintype "passive"))
    )
    (net (code "205") (name "VSSA") (class "Default")
      (node (ref "X8") (pin "43") (pinfunction "22_43") (pintype "passive"))
    )
    (net (code "206") (name "VSSA2") (class "Default")
      (node (ref "X8") (pin "44") (pinfunction "23_44") (pintype "passive"))
    )
  )
)
